# Control_Panel.net
KiCad netlist of a schematic drawn in Altium Designer
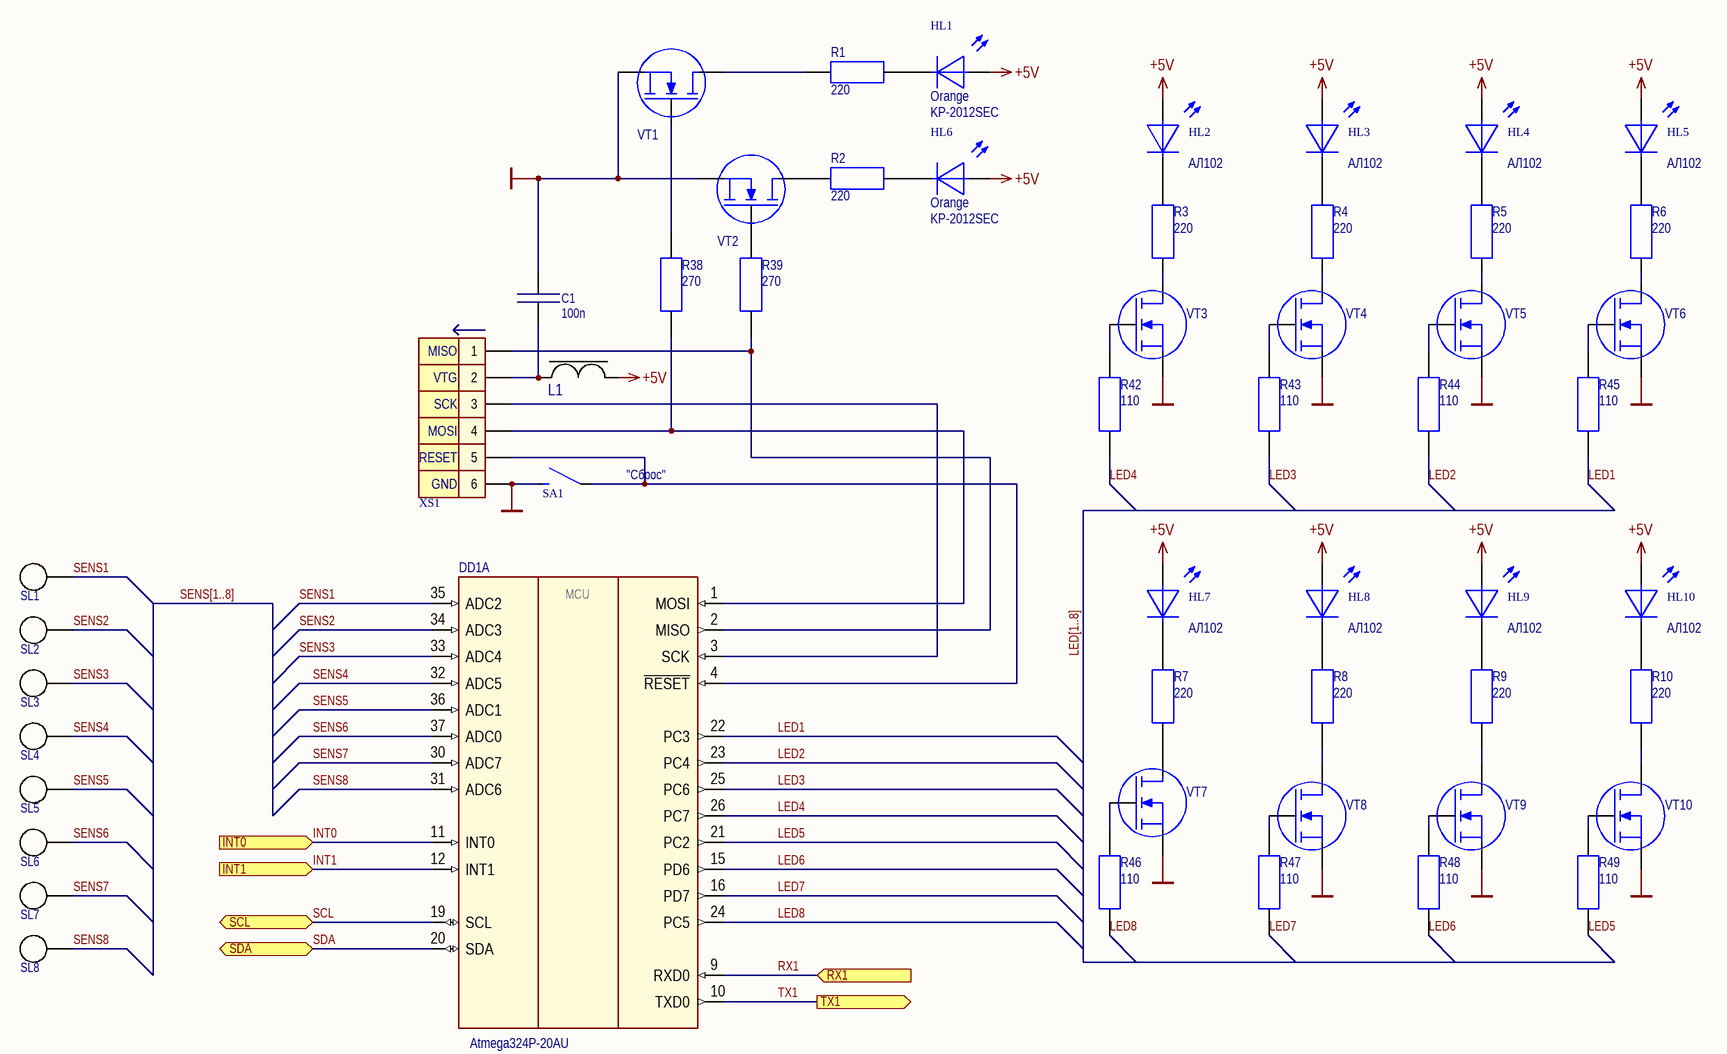
[diagram p0: Control_Panel.SchDoc]

(export (version "E")
  (design (tool "Eeschema 10.0.6"))
  (components
    (comp (ref "C1")
      (value "100n")
      (footprint "SMDRC0805")
      (description "Generic capasitor non-polar")
      (fields (field (name "PARTNUMBER") "Capacitor 0805 100n"))
      (libsource (lib "library") (part "Capacitor"))
    )
    (comp (ref "DD1")
      (value "Atmega324P-20AU")
      (footprint "Atmel Microcontroller 8-Bit Automotive AVR:44ML_M")
      (description "Microcontroller 8-bit")
      (fields (field (name "MANUFACTURER") "Atmel") (field (name "MANUFACTURERPARTNUMBER") "Atmega324P-20AU"))
      (libsource (lib "Microcontrollers") (part "Atmega324P-20AU"))
    )
    (comp (ref "HL1")
      (value "Orange")
      (footprint "Indicator:DIOMELF2012M")
      (description "Diod LED SMD Orange")
      (fields (field (name "MANUFACTURERPARTNUMBER") "KP-2012SEC"))
      (libsource (lib "Indicator") (part "LED1_O"))
    )
    (comp (ref "HL2")
      (value "~")
      (footprint "LED_diode")
      (description "Diod LED")
      (fields (field (name "MANUFACTURER") "СССР") (field (name "MANUFACTURERPARTNUMBER") "АЛ102"))
      (libsource (lib "Indicator") (part "_LED1_АЛ102"))
    )
    (comp (ref "HL3")
      (value "~")
      (footprint "LED_diode")
      (description "Diod LED")
      (fields (field (name "MANUFACTURER") "СССР") (field (name "MANUFACTURERPARTNUMBER") "АЛ102"))
      (libsource (lib "Indicator") (part "_LED1_АЛ102"))
    )
    (comp (ref "HL4")
      (value "~")
      (footprint "LED_diode")
      (description "Diod LED")
      (fields (field (name "MANUFACTURER") "СССР") (field (name "MANUFACTURERPARTNUMBER") "АЛ102"))
      (libsource (lib "Indicator") (part "_LED1_АЛ102"))
    )
    (comp (ref "HL5")
      (value "~")
      (footprint "LED_diode")
      (description "Diod LED")
      (fields (field (name "MANUFACTURER") "СССР") (field (name "MANUFACTURERPARTNUMBER") "АЛ102"))
      (libsource (lib "Indicator") (part "_LED1_АЛ102"))
    )
    (comp (ref "HL6")
      (value "Orange")
      (footprint "Indicator:DIOMELF2012M")
      (description "Diod LED SMD Orange")
      (fields (field (name "MANUFACTURERPARTNUMBER") "KP-2012SEC"))
      (libsource (lib "Indicator") (part "LED1_O"))
    )
    (comp (ref "HL7")
      (value "~")
      (footprint "LED_diode")
      (description "Diod LED")
      (fields (field (name "MANUFACTURER") "СССР") (field (name "MANUFACTURERPARTNUMBER") "АЛ102"))
      (libsource (lib "Indicator") (part "_LED1_АЛ102"))
    )
    (comp (ref "HL8")
      (value "~")
      (footprint "LED_diode")
      (description "Diod LED")
      (fields (field (name "MANUFACTURER") "СССР") (field (name "MANUFACTURERPARTNUMBER") "АЛ102"))
      (libsource (lib "Indicator") (part "_LED1_АЛ102"))
    )
    (comp (ref "HL9")
      (value "~")
      (footprint "LED_diode")
      (description "Diod LED")
      (fields (field (name "MANUFACTURER") "СССР") (field (name "MANUFACTURERPARTNUMBER") "АЛ102"))
      (libsource (lib "Indicator") (part "_LED1_АЛ102"))
    )
    (comp (ref "HL10")
      (value "~")
      (footprint "LED_diode")
      (description "Diod LED")
      (fields (field (name "MANUFACTURER") "СССР") (field (name "MANUFACTURERPARTNUMBER") "АЛ102"))
      (libsource (lib "Indicator") (part "_LED1_АЛ102"))
    )
    (comp (ref "L1")
      (value "MPZ1608S181A")
      (footprint "Inductor:INDC0603X03M")
      (description "Ferrite Bead")
      (libsource (lib "Inductor") (part "Ferrite Bead"))
    )
    (comp (ref "R1")
      (value "220")
      (footprint "SMDRC0805")
      (description "Generic resistor")
      (fields (field (name "PARTNUMBER") "Resistor 0805 220"))
      (libsource (lib "library") (part "Resistor"))
    )
    (comp (ref "R2")
      (value "220")
      (footprint "SMDRC0805")
      (description "Generic resistor")
      (fields (field (name "PARTNUMBER") "Resistor 0805 220"))
      (libsource (lib "library") (part "Resistor"))
    )
    (comp (ref "R3")
      (value "220")
      (footprint "SMDRC0805")
      (description "Generic resistor")
      (fields (field (name "PARTNUMBER") "Resistor 0805 220"))
      (libsource (lib "") (part "Resistor_1"))
    )
    (comp (ref "R4")
      (value "220")
      (footprint "SMDRC0805")
      (description "Generic resistor")
      (fields (field (name "PARTNUMBER") "Resistor 0805 220"))
      (libsource (lib "") (part "Resistor_1"))
    )
    (comp (ref "R5")
      (value "220")
      (footprint "SMDRC0805")
      (description "Generic resistor")
      (fields (field (name "PARTNUMBER") "Resistor 0805 220"))
      (libsource (lib "") (part "Resistor_1"))
    )
    (comp (ref "R6")
      (value "220")
      (footprint "SMDRC0805")
      (description "Generic resistor")
      (fields (field (name "PARTNUMBER") "Resistor 0805 220"))
      (libsource (lib "") (part "Resistor_1"))
    )
    (comp (ref "R7")
      (value "220")
      (footprint "SMDRC0805")
      (description "Generic resistor")
      (fields (field (name "PARTNUMBER") "Resistor 0805 220"))
      (libsource (lib "") (part "Resistor_1"))
    )
    (comp (ref "R8")
      (value "220")
      (footprint "SMDRC0805")
      (description "Generic resistor")
      (fields (field (name "PARTNUMBER") "Resistor 0805 220"))
      (libsource (lib "") (part "Resistor_1"))
    )
    (comp (ref "R9")
      (value "220")
      (footprint "SMDRC0805")
      (description "Generic resistor")
      (fields (field (name "PARTNUMBER") "Resistor 0805 220"))
      (libsource (lib "") (part "Resistor_1"))
    )
    (comp (ref "R10")
      (value "220")
      (footprint "SMDRC0805")
      (description "Generic resistor")
      (fields (field (name "PARTNUMBER") "Resistor 0805 220"))
      (libsource (lib "") (part "Resistor_1"))
    )
    (comp (ref "R38")
      (value "270")
      (footprint "SMDRC0805")
      (description "Generic resistor")
      (fields (field (name "PARTNUMBER") "Resistor 0805 270"))
      (libsource (lib "library") (part "Resistor"))
    )
    (comp (ref "R39")
      (value "270")
      (footprint "SMDRC0805")
      (description "Generic resistor")
      (fields (field (name "PARTNUMBER") "Resistor 0805 270"))
      (libsource (lib "library") (part "Resistor"))
    )
    (comp (ref "R42")
      (value "110")
      (footprint "SMDRC0805")
      (description "Generic resistor")
      (fields (field (name "PARTNUMBER") "Resistor 0805 110"))
      (libsource (lib "library") (part "Resistor"))
    )
    (comp (ref "R43")
      (value "110")
      (footprint "SMDRC0805")
      (description "Generic resistor")
      (fields (field (name "PARTNUMBER") "Resistor 0805 110"))
      (libsource (lib "library") (part "Resistor"))
    )
    (comp (ref "R44")
      (value "110")
      (footprint "SMDRC0805")
      (description "Generic resistor")
      (fields (field (name "PARTNUMBER") "Resistor 0805 110"))
      (libsource (lib "library") (part "Resistor"))
    )
    (comp (ref "R45")
      (value "110")
      (footprint "SMDRC0805")
      (description "Generic resistor")
      (fields (field (name "PARTNUMBER") "Resistor 0805 110"))
      (libsource (lib "library") (part "Resistor"))
    )
    (comp (ref "R46")
      (value "110")
      (footprint "SMDRC0805")
      (description "Generic resistor")
      (fields (field (name "PARTNUMBER") "Resistor 0805 110"))
      (libsource (lib "library") (part "Resistor"))
    )
    (comp (ref "R47")
      (value "110")
      (footprint "SMDRC0805")
      (description "Generic resistor")
      (fields (field (name "PARTNUMBER") "Resistor 0805 110"))
      (libsource (lib "library") (part "Resistor"))
    )
    (comp (ref "R48")
      (value "110")
      (footprint "SMDRC0805")
      (description "Generic resistor")
      (fields (field (name "PARTNUMBER") "Resistor 0805 110"))
      (libsource (lib "library") (part "Resistor"))
    )
    (comp (ref "R49")
      (value "110")
      (footprint "SMDRC0805")
      (description "Generic resistor")
      (fields (field (name "PARTNUMBER") "Resistor 0805 110"))
      (libsource (lib "library") (part "Resistor"))
    )
    (comp (ref "SA1")
      (value "DTSM20-4.3")
      (footprint "Switch:DTSM20")
      (description "Switch open")
      (fields (field (name "MANUFACTURER") "Diptronics"))
      (libsource (lib "Switch") (part "Switch1_DTSM20-4.3"))
    )
    (comp (ref "SL1")
      (value "Touch_sensor")
      (footprint "Sensor:Bolt 6mm")
      (description "Bolt touch sensor")
      (libsource (lib "Sensor") (part "Touch_sensor"))
    )
    (comp (ref "SL2")
      (value "Touch_sensor")
      (footprint "Sensor:Bolt 6mm")
      (description "Bolt touch sensor")
      (libsource (lib "Sensor") (part "Touch_sensor"))
    )
    (comp (ref "SL3")
      (value "Touch_sensor")
      (footprint "Sensor:Bolt 6mm")
      (description "Bolt touch sensor")
      (libsource (lib "Sensor") (part "Touch_sensor"))
    )
    (comp (ref "SL4")
      (value "Touch_sensor")
      (footprint "Sensor:Bolt 6mm")
      (description "Bolt touch sensor")
      (libsource (lib "Sensor") (part "Touch_sensor"))
    )
    (comp (ref "SL5")
      (value "Touch_sensor")
      (footprint "Sensor:Bolt 6mm")
      (description "Bolt touch sensor")
      (libsource (lib "Sensor") (part "Touch_sensor"))
    )
    (comp (ref "SL6")
      (value "Touch_sensor")
      (footprint "Sensor:Bolt 6mm")
      (description "Bolt touch sensor")
      (libsource (lib "Sensor") (part "Touch_sensor"))
    )
    (comp (ref "SL7")
      (value "Touch_sensor")
      (footprint "Sensor:Bolt 6mm")
      (description "Bolt touch sensor")
      (libsource (lib "Sensor") (part "Touch_sensor"))
    )
    (comp (ref "SL8")
      (value "Touch_sensor")
      (footprint "Sensor:Bolt 6mm")
      (description "Bolt touch sensor")
      (libsource (lib "Sensor") (part "Touch_sensor"))
    )
    (comp (ref "VT1")
      (value "2N7002")
      (footprint "Standard:SOT23 (TO-236AB)")
      (description "60V, 300mA N-channel Trench MOSFET")
      (libsource (lib "Transistor") (part "2N7002 n-MOSFET"))
    )
    (comp (ref "VT2")
      (value "2N7002")
      (footprint "Standard:SOT23 (TO-236AB)")
      (description "60V, 300mA N-channel Trench MOSFET")
      (libsource (lib "Transistor") (part "2N7002 n-MOSFET"))
    )
    (comp (ref "VT3")
      (value "2N7002")
      (footprint "Standard:SOT23 (TO-236AB)")
      (description "60V, 300mA N-channel Trench MOSFET")
      (libsource (lib "Transistor") (part "2N7002 n-MOSFET"))
    )
    (comp (ref "VT4")
      (value "2N7002")
      (footprint "Standard:SOT23 (TO-236AB)")
      (description "60V, 300mA N-channel Trench MOSFET")
      (libsource (lib "Transistor") (part "2N7002 n-MOSFET"))
    )
    (comp (ref "VT5")
      (value "2N7002")
      (footprint "Standard:SOT23 (TO-236AB)")
      (description "60V, 300mA N-channel Trench MOSFET")
      (libsource (lib "Transistor") (part "2N7002 n-MOSFET"))
    )
    (comp (ref "VT6")
      (value "2N7002")
      (footprint "Standard:SOT23 (TO-236AB)")
      (description "60V, 300mA N-channel Trench MOSFET")
      (libsource (lib "Transistor") (part "2N7002 n-MOSFET"))
    )
    (comp (ref "VT7")
      (value "2N7002")
      (footprint "Standard:SOT23 (TO-236AB)")
      (description "60V, 300mA N-channel Trench MOSFET")
      (libsource (lib "Transistor") (part "2N7002 n-MOSFET"))
    )
    (comp (ref "VT8")
      (value "2N7002")
      (footprint "Standard:SOT23 (TO-236AB)")
      (description "60V, 300mA N-channel Trench MOSFET")
      (libsource (lib "Transistor") (part "2N7002 n-MOSFET"))
    )
    (comp (ref "VT9")
      (value "2N7002")
      (footprint "Standard:SOT23 (TO-236AB)")
      (description "60V, 300mA N-channel Trench MOSFET")
      (libsource (lib "Transistor") (part "2N7002 n-MOSFET"))
    )
    (comp (ref "VT10")
      (value "2N7002")
      (footprint "Standard:SOT23 (TO-236AB)")
      (description "60V, 300mA N-channel Trench MOSFET")
      (libsource (lib "Transistor") (part "2N7002 n-MOSFET"))
    )
    (comp (ref "XS1")
      (value "IDC-06M")
      (footprint "Connector:IDC-06M")
      (description "SPI connector")
      (libsource (lib "Connector") (part "Con6_M IDC-06M_SPI"))
    )
  )
  (nets
    (net (code "1") (name "+5V") (class "Default")
      (node (ref "HL1") (pin "1") (pinfunction "1_1") (pintype "passive"))
      (node (ref "HL10") (pin "A") (pinfunction "A_A") (pintype "passive"))
      (node (ref "HL2") (pin "A") (pinfunction "A_A") (pintype "passive"))
      (node (ref "HL3") (pin "A") (pinfunction "A_A") (pintype "passive"))
      (node (ref "HL4") (pin "A") (pinfunction "A_A") (pintype "passive"))
      (node (ref "HL5") (pin "A") (pinfunction "A_A") (pintype "passive"))
      (node (ref "HL6") (pin "1") (pinfunction "1_1") (pintype "passive"))
      (node (ref "HL7") (pin "A") (pinfunction "A_A") (pintype "passive"))
      (node (ref "HL8") (pin "A") (pinfunction "A_A") (pintype "passive"))
      (node (ref "HL9") (pin "A") (pinfunction "A_A") (pintype "passive"))
      (node (ref "L1") (pin "1") (pinfunction "1_1") (pintype "passive"))
    )
    (net (code "2") (name "/INT0") (class "Default")
      (node (ref "DD1") (pin "11") (pinfunction "INT0_11") (pintype "input"))
    )
    (net (code "3") (name "/INT1") (class "Default")
      (node (ref "DD1") (pin "12") (pinfunction "INT1_12") (pintype "input"))
    )
    (net (code "4") (name "/LED1") (class "Default")
      (node (ref "DD1") (pin "22") (pinfunction "PC3_22") (pintype "output"))
      (node (ref "R45") (pin "1") (pinfunction "1_1") (pintype "passive"))
    )
    (net (code "5") (name "/LED2") (class "Default")
      (node (ref "DD1") (pin "23") (pinfunction "PC4_23") (pintype "output"))
      (node (ref "R44") (pin "1") (pinfunction "1_1") (pintype "passive"))
    )
    (net (code "6") (name "/LED3") (class "Default")
      (node (ref "DD1") (pin "25") (pinfunction "PC6_25") (pintype "output"))
      (node (ref "R43") (pin "1") (pinfunction "1_1") (pintype "passive"))
    )
    (net (code "7") (name "/LED4") (class "Default")
      (node (ref "DD1") (pin "26") (pinfunction "PC7_26") (pintype "output"))
      (node (ref "R42") (pin "1") (pinfunction "1_1") (pintype "passive"))
    )
    (net (code "8") (name "/LED5") (class "Default")
      (node (ref "DD1") (pin "21") (pinfunction "PC2_21") (pintype "output"))
      (node (ref "R49") (pin "1") (pinfunction "1_1") (pintype "passive"))
    )
    (net (code "9") (name "/LED6") (class "Default")
      (node (ref "DD1") (pin "15") (pinfunction "PD6_15") (pintype "output"))
      (node (ref "R48") (pin "1") (pinfunction "1_1") (pintype "passive"))
    )
    (net (code "10") (name "/LED7") (class "Default")
      (node (ref "DD1") (pin "16") (pinfunction "PD7_16") (pintype "output"))
      (node (ref "R47") (pin "1") (pinfunction "1_1") (pintype "passive"))
    )
    (net (code "11") (name "/LED8") (class "Default")
      (node (ref "DD1") (pin "24") (pinfunction "PC5_24") (pintype "output"))
      (node (ref "R46") (pin "1") (pinfunction "1_1") (pintype "passive"))
    )
    (net (code "13") (name "/RX1") (class "Default")
      (node (ref "DD1") (pin "9") (pinfunction "RXD0_9") (pintype "input"))
    )
    (net (code "14") (name "/SCL") (class "Default")
      (node (ref "DD1") (pin "19") (pinfunction "SCL_19") (pintype "bidirectional"))
    )
    (net (code "15") (name "/SDA") (class "Default")
      (node (ref "DD1") (pin "20") (pinfunction "SDA_20") (pintype "bidirectional"))
    )
    (net (code "16") (name "/SENS1") (class "Default")
      (node (ref "DD1") (pin "35") (pinfunction "ADC2_35") (pintype "input"))
      (node (ref "SL1") (pin "1") (pinfunction "1_1") (pintype "passive"))
    )
    (net (code "17") (name "/SENS2") (class "Default")
      (node (ref "DD1") (pin "34") (pinfunction "ADC3_34") (pintype "input"))
      (node (ref "SL2") (pin "1") (pinfunction "1_1") (pintype "passive"))
    )
    (net (code "18") (name "/SENS3") (class "Default")
      (node (ref "DD1") (pin "33") (pinfunction "ADC4_33") (pintype "input"))
      (node (ref "SL3") (pin "1") (pinfunction "1_1") (pintype "passive"))
    )
    (net (code "19") (name "/SENS4") (class "Default")
      (node (ref "DD1") (pin "32") (pinfunction "ADC5_32") (pintype "input"))
      (node (ref "SL4") (pin "1") (pinfunction "1_1") (pintype "passive"))
    )
    (net (code "20") (name "/SENS5") (class "Default")
      (node (ref "DD1") (pin "36") (pinfunction "ADC1_36") (pintype "input"))
      (node (ref "SL5") (pin "1") (pinfunction "1_1") (pintype "passive"))
    )
    (net (code "21") (name "/SENS6") (class "Default")
      (node (ref "DD1") (pin "37") (pinfunction "ADC0_37") (pintype "input"))
      (node (ref "SL6") (pin "1") (pinfunction "1_1") (pintype "passive"))
    )
    (net (code "22") (name "/SENS7") (class "Default")
      (node (ref "DD1") (pin "30") (pinfunction "ADC7_30") (pintype "input"))
      (node (ref "SL7") (pin "1") (pinfunction "1_1") (pintype "passive"))
    )
    (net (code "23") (name "/SENS8") (class "Default")
      (node (ref "DD1") (pin "31") (pinfunction "ADC6_31") (pintype "input"))
      (node (ref "SL8") (pin "1") (pinfunction "1_1") (pintype "passive"))
    )
    (net (code "25") (name "/TX1") (class "Default")
      (node (ref "DD1") (pin "10") (pinfunction "TXD0_10") (pintype "output"))
    )
    (net (code "26") (name "GND") (class "Default")
      (node (ref "C1") (pin "2") (pintype "passive"))
      (node (ref "SA1") (pin "2") (pinfunction "2_2") (pintype "passive"))
      (node (ref "VT1") (pin "2") (pinfunction "S_2") (pintype "passive"))
      (node (ref "VT10") (pin "2") (pinfunction "S_2") (pintype "passive"))
      (node (ref "VT2") (pin "2") (pinfunction "S_2") (pintype "passive"))
      (node (ref "VT3") (pin "2") (pinfunction "S_2") (pintype "passive"))
      (node (ref "VT4") (pin "2") (pinfunction "S_2") (pintype "passive"))
      (node (ref "VT5") (pin "2") (pinfunction "S_2") (pintype "passive"))
      (node (ref "VT6") (pin "2") (pinfunction "S_2") (pintype "passive"))
      (node (ref "VT7") (pin "2") (pinfunction "S_2") (pintype "passive"))
      (node (ref "VT8") (pin "2") (pinfunction "S_2") (pintype "passive"))
      (node (ref "VT9") (pin "2") (pinfunction "S_2") (pintype "passive"))
      (node (ref "XS1") (pin "6") (pinfunction "6_6") (pintype "passive"))
    )
    (net (code "27") (name "Net-(C1-Pad1)") (class "Default")
      (node (ref "C1") (pin "1") (pintype "passive"))
      (node (ref "L1") (pin "2") (pinfunction "2_2") (pintype "passive"))
      (node (ref "XS1") (pin "2") (pinfunction "2_2") (pintype "passive"))
    )
    (net (code "28") (name "Net-(DD1A-MISO)") (class "Default")
      (node (ref "DD1") (pin "2") (pinfunction "MISO_2") (pintype "output"))
      (node (ref "R39") (pin "1") (pinfunction "1_1") (pintype "passive"))
      (node (ref "XS1") (pin "1") (pinfunction "1_1") (pintype "passive"))
    )
    (net (code "29") (name "Net-(DD1A-MOSI)") (class "Default")
      (node (ref "DD1") (pin "1") (pinfunction "MOSI_1") (pintype "input"))
      (node (ref "R38") (pin "1") (pinfunction "1_1") (pintype "passive"))
      (node (ref "XS1") (pin "4") (pinfunction "4_4") (pintype "passive"))
    )
    (net (code "30") (name "Net-(DD1A-SCK)") (class "Default")
      (node (ref "DD1") (pin "3") (pinfunction "SCK_3") (pintype "input"))
      (node (ref "XS1") (pin "3") (pinfunction "3_3") (pintype "passive"))
    )
    (net (code "31") (name "Net-(DD1A-~{RESET})") (class "Default")
      (node (ref "DD1") (pin "4") (pinfunction "~{RESET}_4") (pintype "input"))
      (node (ref "SA1") (pin "1") (pinfunction "1_1") (pintype "passive"))
      (node (ref "XS1") (pin "5") (pinfunction "5_5") (pintype "passive"))
    )
    (net (code "32") (name "Net-(HL1-Pad2)") (class "Default")
      (node (ref "HL1") (pin "2") (pinfunction "2_2") (pintype "passive"))
      (node (ref "R1") (pin "2") (pinfunction "2_2") (pintype "passive"))
    )
    (net (code "33") (name "Net-(HL2-PadK)") (class "Default")
      (node (ref "HL2") (pin "K") (pinfunction "K_K") (pintype "passive"))
      (node (ref "R3") (pin "2") (pinfunction "2_2") (pintype "passive"))
    )
    (net (code "34") (name "Net-(HL3-PadK)") (class "Default")
      (node (ref "HL3") (pin "K") (pinfunction "K_K") (pintype "passive"))
      (node (ref "R4") (pin "2") (pinfunction "2_2") (pintype "passive"))
    )
    (net (code "35") (name "Net-(HL4-PadK)") (class "Default")
      (node (ref "HL4") (pin "K") (pinfunction "K_K") (pintype "passive"))
      (node (ref "R5") (pin "2") (pinfunction "2_2") (pintype "passive"))
    )
    (net (code "36") (name "Net-(HL5-PadK)") (class "Default")
      (node (ref "HL5") (pin "K") (pinfunction "K_K") (pintype "passive"))
      (node (ref "R6") (pin "2") (pinfunction "2_2") (pintype "passive"))
    )
    (net (code "37") (name "Net-(HL6-Pad2)") (class "Default")
      (node (ref "HL6") (pin "2") (pinfunction "2_2") (pintype "passive"))
      (node (ref "R2") (pin "2") (pinfunction "2_2") (pintype "passive"))
    )
    (net (code "38") (name "Net-(HL7-PadK)") (class "Default")
      (node (ref "HL7") (pin "K") (pinfunction "K_K") (pintype "passive"))
      (node (ref "R7") (pin "2") (pinfunction "2_2") (pintype "passive"))
    )
    (net (code "39") (name "Net-(HL8-PadK)") (class "Default")
      (node (ref "HL8") (pin "K") (pinfunction "K_K") (pintype "passive"))
      (node (ref "R8") (pin "2") (pinfunction "2_2") (pintype "passive"))
    )
    (net (code "40") (name "Net-(HL9-PadK)") (class "Default")
      (node (ref "HL9") (pin "K") (pinfunction "K_K") (pintype "passive"))
      (node (ref "R9") (pin "2") (pinfunction "2_2") (pintype "passive"))
    )
    (net (code "41") (name "Net-(HL10-PadK)") (class "Default")
      (node (ref "HL10") (pin "K") (pinfunction "K_K") (pintype "passive"))
      (node (ref "R10") (pin "2") (pinfunction "2_2") (pintype "passive"))
    )
    (net (code "42") (name "Net-(VT1-D)") (class "Default")
      (node (ref "R1") (pin "1") (pinfunction "1_1") (pintype "passive"))
      (node (ref "VT1") (pin "3") (pinfunction "D_3") (pintype "passive"))
    )
    (net (code "43") (name "Net-(VT1-G)") (class "Default")
      (node (ref "R38") (pin "2") (pinfunction "2_2") (pintype "passive"))
      (node (ref "VT1") (pin "1") (pinfunction "G_1") (pintype "passive"))
    )
    (net (code "44") (name "Net-(VT2-D)") (class "Default")
      (node (ref "R2") (pin "1") (pinfunction "1_1") (pintype "passive"))
      (node (ref "VT2") (pin "3") (pinfunction "D_3") (pintype "passive"))
    )
    (net (code "45") (name "Net-(VT2-G)") (class "Default")
      (node (ref "R39") (pin "2") (pinfunction "2_2") (pintype "passive"))
      (node (ref "VT2") (pin "1") (pinfunction "G_1") (pintype "passive"))
    )
    (net (code "46") (name "Net-(VT3-D)") (class "Default")
      (node (ref "R3") (pin "1") (pinfunction "1_1") (pintype "passive"))
      (node (ref "VT3") (pin "3") (pinfunction "D_3") (pintype "passive"))
    )
    (net (code "47") (name "Net-(VT3-G)") (class "Default")
      (node (ref "R42") (pin "2") (pinfunction "2_2") (pintype "passive"))
      (node (ref "VT3") (pin "1") (pinfunction "G_1") (pintype "passive"))
    )
    (net (code "48") (name "Net-(VT4-D)") (class "Default")
      (node (ref "R4") (pin "1") (pinfunction "1_1") (pintype "passive"))
      (node (ref "VT4") (pin "3") (pinfunction "D_3") (pintype "passive"))
    )
    (net (code "49") (name "Net-(VT4-G)") (class "Default")
      (node (ref "R43") (pin "2") (pinfunction "2_2") (pintype "passive"))
      (node (ref "VT4") (pin "1") (pinfunction "G_1") (pintype "passive"))
    )
    (net (code "50") (name "Net-(VT5-D)") (class "Default")
      (node (ref "R5") (pin "1") (pinfunction "1_1") (pintype "passive"))
      (node (ref "VT5") (pin "3") (pinfunction "D_3") (pintype "passive"))
    )
    (net (code "51") (name "Net-(VT5-G)") (class "Default")
      (node (ref "R44") (pin "2") (pinfunction "2_2") (pintype "passive"))
      (node (ref "VT5") (pin "1") (pinfunction "G_1") (pintype "passive"))
    )
    (net (code "52") (name "Net-(VT6-D)") (class "Default")
      (node (ref "R6") (pin "1") (pinfunction "1_1") (pintype "passive"))
      (node (ref "VT6") (pin "3") (pinfunction "D_3") (pintype "passive"))
    )
    (net (code "53") (name "Net-(VT6-G)") (class "Default")
      (node (ref "R45") (pin "2") (pinfunction "2_2") (pintype "passive"))
      (node (ref "VT6") (pin "1") (pinfunction "G_1") (pintype "passive"))
    )
    (net (code "54") (name "Net-(VT7-D)") (class "Default")
      (node (ref "R7") (pin "1") (pinfunction "1_1") (pintype "passive"))
      (node (ref "VT7") (pin "3") (pinfunction "D_3") (pintype "passive"))
    )
    (net (code "55") (name "Net-(VT7-G)") (class "Default")
      (node (ref "R46") (pin "2") (pinfunction "2_2") (pintype "passive"))
      (node (ref "VT7") (pin "1") (pinfunction "G_1") (pintype "passive"))
    )
    (net (code "56") (name "Net-(VT8-D)") (class "Default")
      (node (ref "R8") (pin "1") (pinfunction "1_1") (pintype "passive"))
      (node (ref "VT8") (pin "3") (pinfunction "D_3") (pintype "passive"))
    )
    (net (code "57") (name "Net-(VT8-G)") (class "Default")
      (node (ref "R47") (pin "2") (pinfunction "2_2") (pintype "passive"))
      (node (ref "VT8") (pin "1") (pinfunction "G_1") (pintype "passive"))
    )
    (net (code "58") (name "Net-(VT9-D)") (class "Default")
      (node (ref "R9") (pin "1") (pinfunction "1_1") (pintype "passive"))
      (node (ref "VT9") (pin "3") (pinfunction "D_3") (pintype "passive"))
    )
    (net (code "59") (name "Net-(VT9-G)") (class "Default")
      (node (ref "R48") (pin "2") (pinfunction "2_2") (pintype "passive"))
      (node (ref "VT9") (pin "1") (pinfunction "G_1") (pintype "passive"))
    )
    (net (code "60") (name "Net-(VT10-D)") (class "Default")
      (node (ref "R10") (pin "1") (pinfunction "1_1") (pintype "passive"))
      (node (ref "VT10") (pin "3") (pinfunction "D_3") (pintype "passive"))
    )
    (net (code "61") (name "Net-(VT10-G)") (class "Default")
      (node (ref "R49") (pin "2") (pinfunction "2_2") (pintype "passive"))
      (node (ref "VT10") (pin "1") (pinfunction "G_1") (pintype "passive"))
    )
  )
)
